# sch.net
KiCad netlist of a schematic drawn in EasyEDA
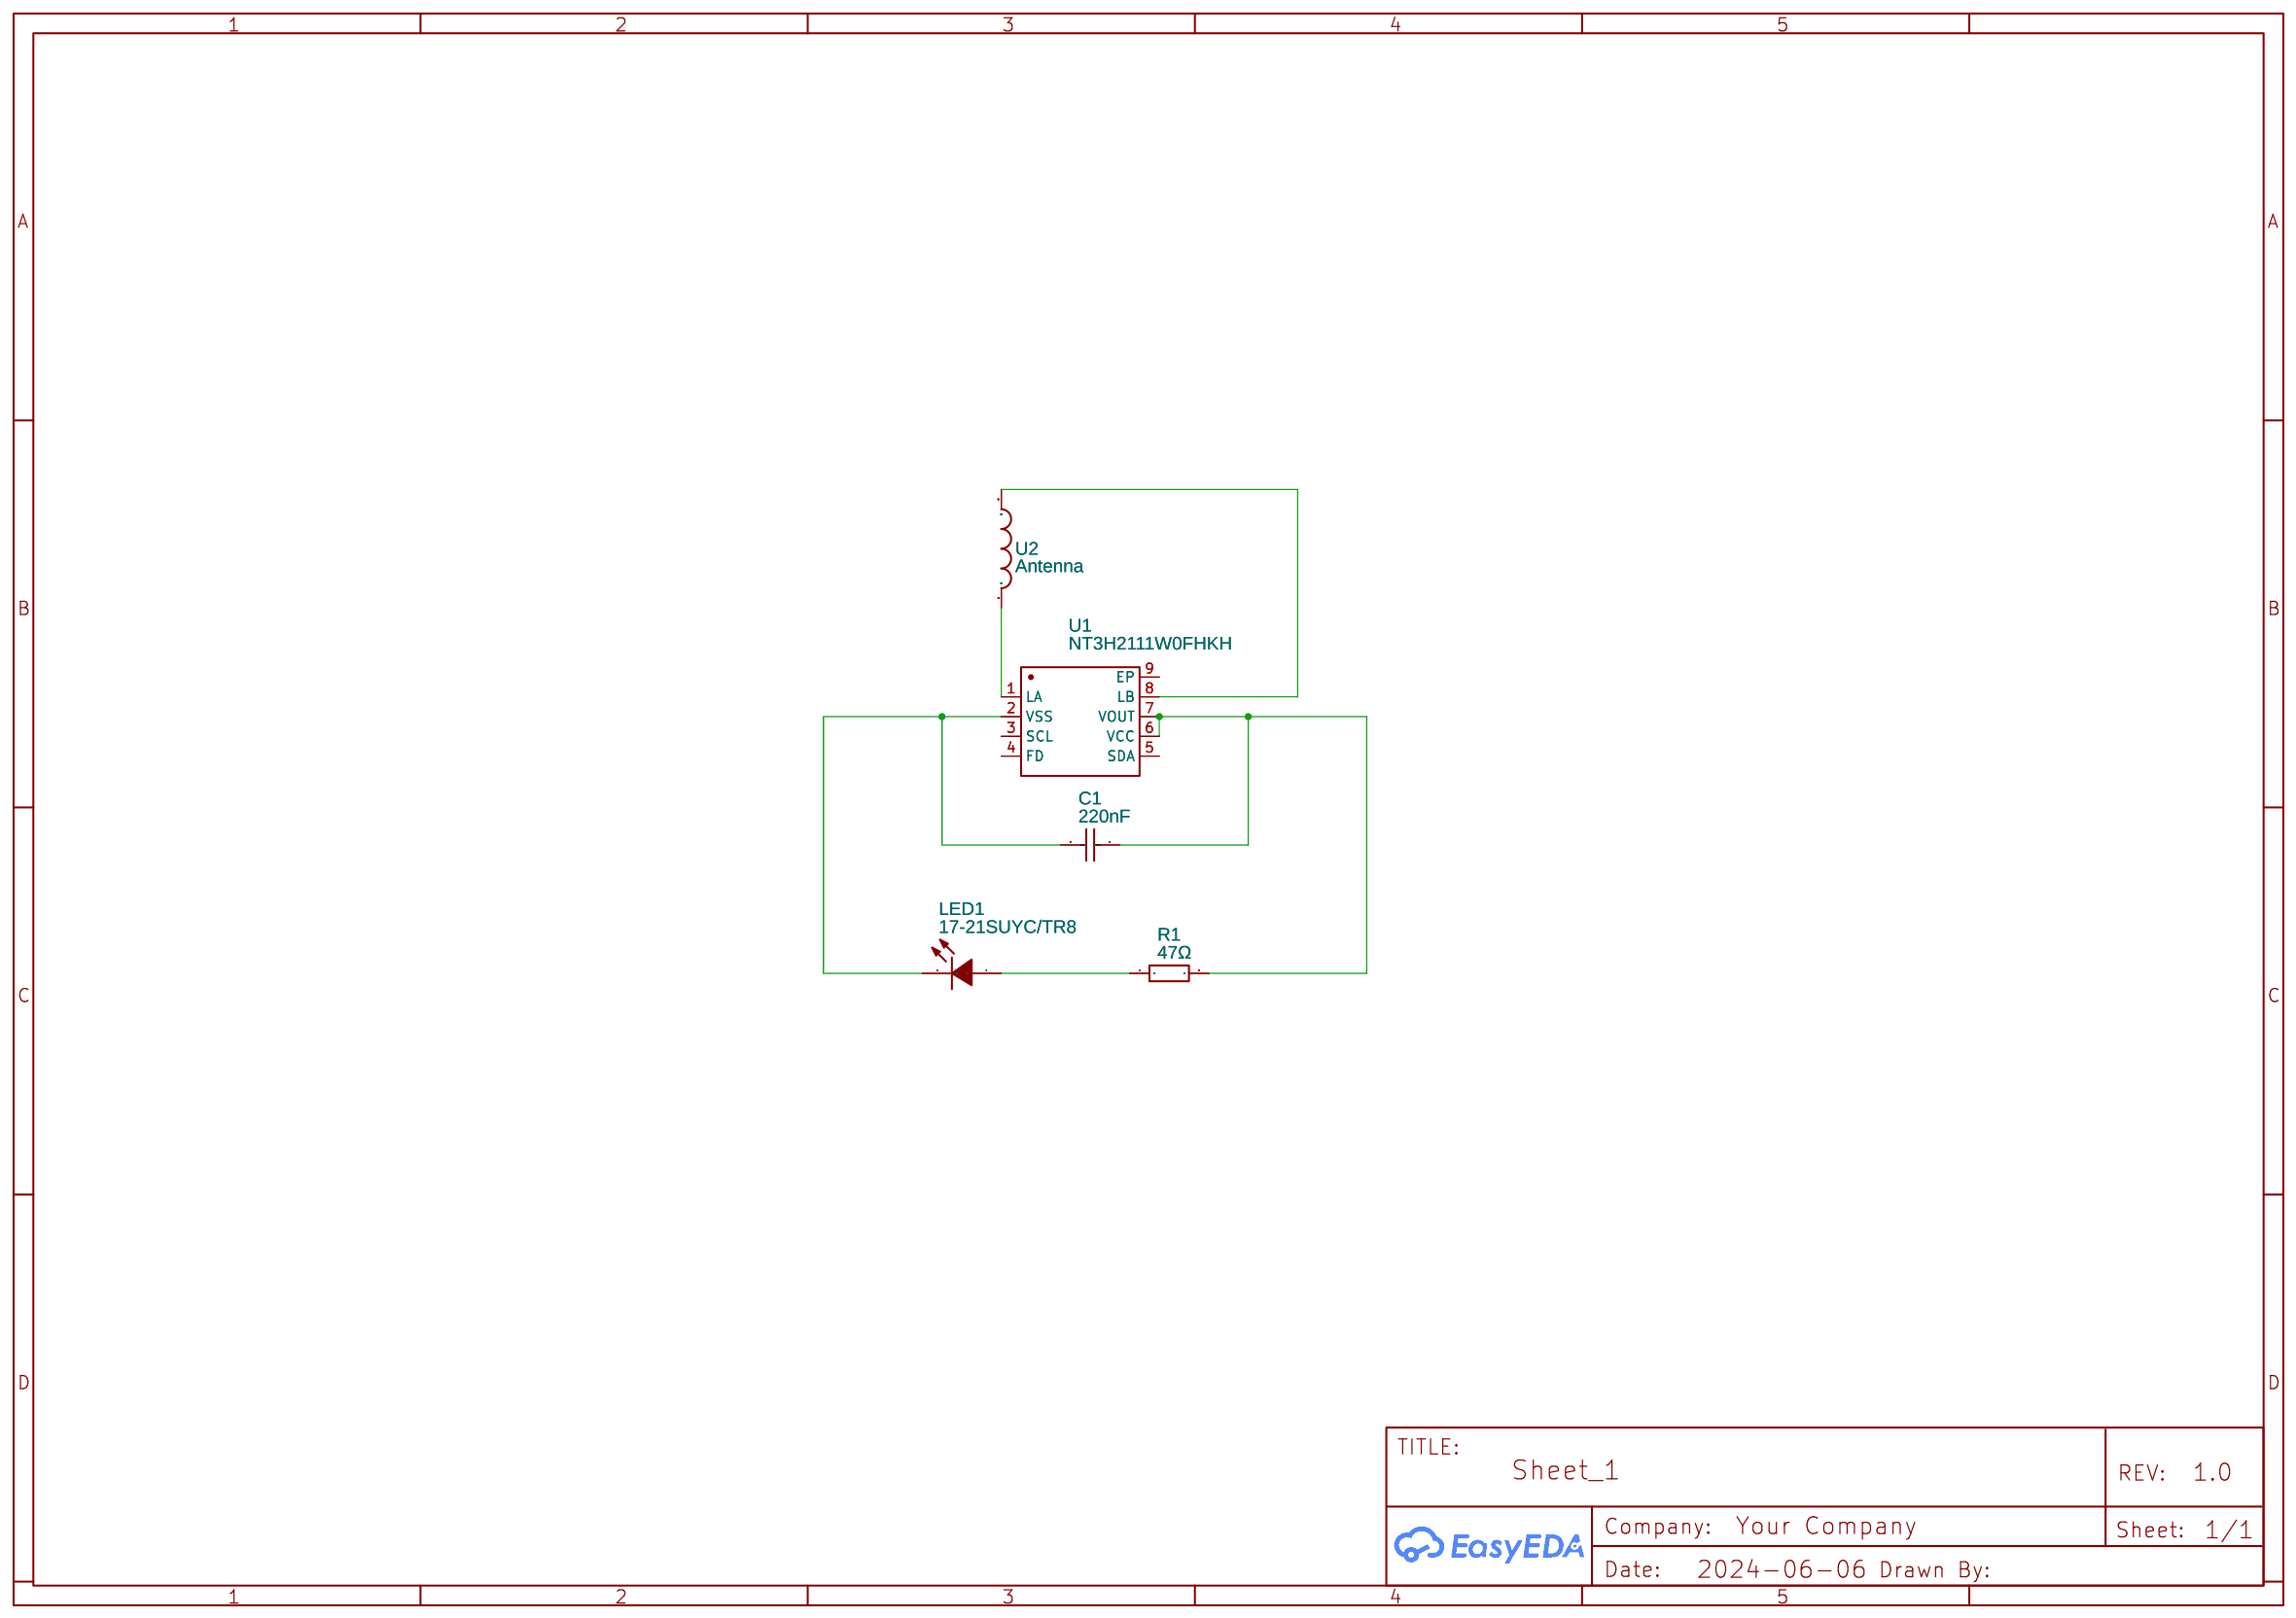
[diagram p0: schematic sheet]

(export (version "E")
  (design (tool "Eeschema 10.0.6"))
  (components
    (comp (ref "C1")
      (value "220nF")
      (fields
        (field (name "Manufacturer Part") "CL10B224KA8NNNC")
        (field (name "Manufacturer") "SAMSUNG(三星)")
      )
      (libsource (lib "") (part "CL10B224KA8NNNC"))
    )
    (comp (ref "LED1")
      (value "17-21SUYC/TR8")
      (fields (field (name "Manufacturer Part") "KT-0805黄灯") (field (name "Manufacturer") "KENTO"))
      (libsource (lib "") (part "17-21SUYC/TR8"))
    )
    (comp (ref "R1")
      (value "47Ω")
      (fields
        (field (name "Manufacturer Part") "0603WAF470JT5E")
        (field (name "Manufacturer") "UNI-ROYAL(厚声)")
      )
      (libsource (lib "") (part "0603WAF470JT5E"))
    )
    (comp (ref "U1")
      (value "NT3H2111W0FHKH")
      (fields (field (name "Manufacturer") "NXP(恩智浦)"))
      (libsource (lib "") (part "NT3H2111W0FHKH"))
    )
    (comp (ref "U2") (value "Antenna") (libsource (lib "") (part "Antenna")))
  )
  (nets
    (net (code "1") (name "Net-(LED1-+)") (class "Default")
      (node (ref "LED1") (pin "1") (pinfunction "+_1") (pintype "unspecified"))
      (node (ref "R1") (pin "1") (pinfunction "1_1") (pintype "input"))
    )
    (net (code "2") (name "Net-(LED1--)") (class "Default")
      (node (ref "C1") (pin "1") (pinfunction "1_1") (pintype "input"))
      (node (ref "LED1") (pin "2") (pinfunction "-_2") (pintype "unspecified"))
      (node (ref "U1") (pin "2") (pinfunction "VSS_2") (pintype "unspecified"))
    )
    (net (code "3") (name "Net-(U1-LA)") (class "Default")
      (node (ref "U1") (pin "1") (pinfunction "LA_1") (pintype "unspecified"))
      (node (ref "U2") (pin "P$1") (pinfunction "P$1_P$1") (pintype "unspecified"))
    )
    (net (code "4") (name "Net-(U1-LB)") (class "Default")
      (node (ref "U1") (pin "8") (pinfunction "LB_8") (pintype "unspecified"))
      (node (ref "U2") (pin "P$2") (pinfunction "P$2_P$2") (pintype "unspecified"))
    )
    (net (code "5") (name "Net-(U1-VCC)") (class "Default")
      (node (ref "C1") (pin "2") (pinfunction "2_2") (pintype "input"))
      (node (ref "R1") (pin "2") (pinfunction "2_2") (pintype "input"))
      (node (ref "U1") (pin "6") (pinfunction "VCC_6") (pintype "unspecified"))
      (node (ref "U1") (pin "7") (pinfunction "VOUT_7") (pintype "unspecified"))
    )
    (net (code "6") (name "unconnected-(U1-EP-Pad9)") (class "Default")
      (node (ref "U1") (pin "9") (pinfunction "EP_9") (pintype "unspecified"))
    )
    (net (code "7") (name "unconnected-(U1-FD-Pad4)") (class "Default")
      (node (ref "U1") (pin "4") (pinfunction "FD_4") (pintype "unspecified"))
    )
    (net (code "8") (name "unconnected-(U1-SCL-Pad3)") (class "Default")
      (node (ref "U1") (pin "3") (pinfunction "SCL_3") (pintype "unspecified"))
    )
    (net (code "9") (name "unconnected-(U1-SDA-Pad5)") (class "Default")
      (node (ref "U1") (pin "5") (pinfunction "SDA_5") (pintype "unspecified"))
    )
  )
)
